# Bluetooth_UEXT.net
KiCad netlist of a schematic drawn in EAGLE
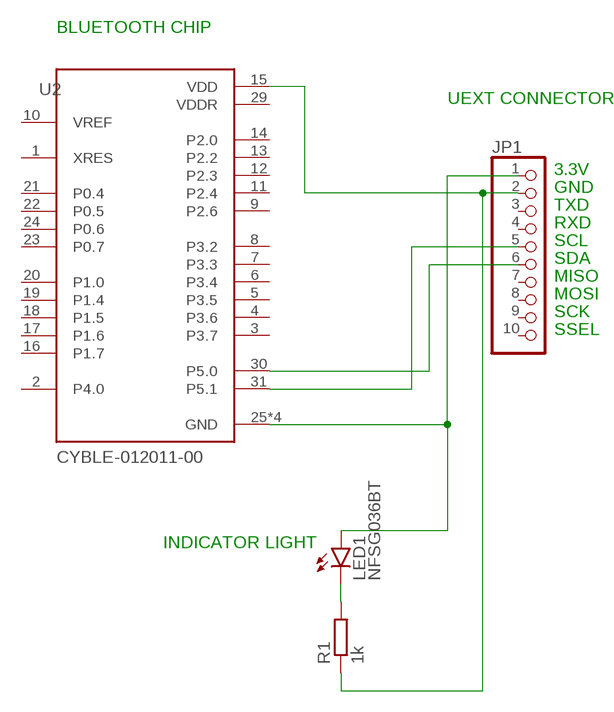
[diagram p0: schematic, sheet 1]

(export (version "E")
  (design (tool "Eeschema 10.0.6"))
  (components
    (comp (ref "JP1")
      (value "PINHD-1X10/90")
      (footprint "eagle-import:1X10_90")
      (libsource (lib "eagle-import") (part "PINHD-1X10/90"))
    )
    (comp (ref "LED1")
      (value "NFSG036BT")
      (footprint "eagle-import:NFSG036BT")
      (libsource (lib "eagle-import") (part "NFSG036BT"))
    )
    (comp (ref "R1")
      (value "1k")
      (footprint "eagle-import:M1206")
      (libsource (lib "eagle-import") (part "R-EU_M1206"))
    )
    (comp (ref "U2")
      (value "CYBLE-012011-00")
      (footprint "eagle-import:XCVR_CYBLE-012011-00")
      (fields (field (name "MF") "Cypress Semiconductor"))
      (libsource (lib "eagle-import") (part "CYBLE-012011-00"))
    )
  )
  (nets
    (net (code "1") (name "/VDDR") (class "Default")
      (node (ref "U2") (pin "29") (pinfunction "VDDR_29") (pintype "power_in"))
    )
    (net (code "2") (name "Net-(JP1-Pad1)") (class "Default")
      (node (ref "JP1") (pin "1") (pinfunction "1_1") (pintype "passive"))
      (node (ref "LED1") (pin "A") (pinfunction "A_A") (pintype "passive"))
      (node (ref "U2") (pin "25") (pinfunction "GND_25") (pintype "power_in"))
      (node (ref "U2") (pin "26") (pinfunction "GND_26") (pintype "power_in"))
      (node (ref "U2") (pin "27") (pinfunction "GND_27") (pintype "power_in"))
      (node (ref "U2") (pin "28") (pinfunction "GND_28") (pintype "power_in"))
    )
    (net (code "3") (name "Net-(LED1-PadC)") (class "Default")
      (node (ref "LED1") (pin "C") (pinfunction "C_C") (pintype "passive"))
      (node (ref "R1") (pin "2") (pinfunction "2_2") (pintype "passive"))
    )
    (net (code "4") (name "Net-(U2-P5.0)") (class "Default")
      (node (ref "JP1") (pin "6") (pinfunction "6_6") (pintype "passive"))
      (node (ref "U2") (pin "30") (pinfunction "P5.0_30") (pintype "bidirectional"))
    )
    (net (code "5") (name "Net-(U2-P5.1)") (class "Default")
      (node (ref "JP1") (pin "5") (pinfunction "5_5") (pintype "passive"))
      (node (ref "U2") (pin "31") (pinfunction "P5.1_31") (pintype "bidirectional"))
    )
    (net (code "6") (name "Net-(U2-VDD)") (class "Default")
      (node (ref "JP1") (pin "2") (pinfunction "2_2") (pintype "passive"))
      (node (ref "R1") (pin "1") (pinfunction "1_1") (pintype "passive"))
      (node (ref "U2") (pin "15") (pinfunction "VDD_15") (pintype "power_in"))
    )
    (net (code "7") (name "unconnected-(JP1-Pad3)") (class "Default")
      (node (ref "JP1") (pin "3") (pinfunction "3_3") (pintype "passive"))
    )
    (net (code "8") (name "unconnected-(JP1-Pad4)") (class "Default")
      (node (ref "JP1") (pin "4") (pinfunction "4_4") (pintype "passive"))
    )
    (net (code "9") (name "unconnected-(JP1-Pad7)") (class "Default")
      (node (ref "JP1") (pin "7") (pinfunction "7_7") (pintype "passive"))
    )
    (net (code "10") (name "unconnected-(JP1-Pad8)") (class "Default")
      (node (ref "JP1") (pin "8") (pinfunction "8_8") (pintype "passive"))
    )
    (net (code "11") (name "unconnected-(JP1-Pad9)") (class "Default")
      (node (ref "JP1") (pin "9") (pinfunction "9_9") (pintype "passive"))
    )
    (net (code "12") (name "unconnected-(JP1-Pad10)") (class "Default")
      (node (ref "JP1") (pin "10") (pinfunction "10_10") (pintype "passive"))
    )
    (net (code "13") (name "unconnected-(U2-P0.4-Pad21)") (class "Default")
      (node (ref "U2") (pin "21") (pinfunction "P0.4_21") (pintype "bidirectional"))
    )
    (net (code "14") (name "unconnected-(U2-P0.5-Pad22)") (class "Default")
      (node (ref "U2") (pin "22") (pinfunction "P0.5_22") (pintype "bidirectional"))
    )
    (net (code "15") (name "unconnected-(U2-P0.6-Pad24)") (class "Default")
      (node (ref "U2") (pin "24") (pinfunction "P0.6_24") (pintype "bidirectional"))
    )
    (net (code "16") (name "unconnected-(U2-P0.7-Pad23)") (class "Default")
      (node (ref "U2") (pin "23") (pinfunction "P0.7_23") (pintype "bidirectional"))
    )
    (net (code "17") (name "unconnected-(U2-P1.0-Pad20)") (class "Default")
      (node (ref "U2") (pin "20") (pinfunction "P1.0_20") (pintype "bidirectional"))
    )
    (net (code "18") (name "unconnected-(U2-P1.4-Pad19)") (class "Default")
      (node (ref "U2") (pin "19") (pinfunction "P1.4_19") (pintype "bidirectional"))
    )
    (net (code "19") (name "unconnected-(U2-P1.5-Pad18)") (class "Default")
      (node (ref "U2") (pin "18") (pinfunction "P1.5_18") (pintype "bidirectional"))
    )
    (net (code "20") (name "unconnected-(U2-P1.6-Pad17)") (class "Default")
      (node (ref "U2") (pin "17") (pinfunction "P1.6_17") (pintype "bidirectional"))
    )
    (net (code "21") (name "unconnected-(U2-P1.7-Pad16)") (class "Default")
      (node (ref "U2") (pin "16") (pinfunction "P1.7_16") (pintype "bidirectional"))
    )
    (net (code "22") (name "unconnected-(U2-P2.0-Pad14)") (class "Default")
      (node (ref "U2") (pin "14") (pinfunction "P2.0_14") (pintype "bidirectional"))
    )
    (net (code "23") (name "unconnected-(U2-P2.2-Pad13)") (class "Default")
      (node (ref "U2") (pin "13") (pinfunction "P2.2_13") (pintype "bidirectional"))
    )
    (net (code "24") (name "unconnected-(U2-P2.3-Pad12)") (class "Default")
      (node (ref "U2") (pin "12") (pinfunction "P2.3_12") (pintype "bidirectional"))
    )
    (net (code "25") (name "unconnected-(U2-P2.4-Pad11)") (class "Default")
      (node (ref "U2") (pin "11") (pinfunction "P2.4_11") (pintype "bidirectional"))
    )
    (net (code "26") (name "unconnected-(U2-P2.6-Pad9)") (class "Default")
      (node (ref "U2") (pin "9") (pinfunction "P2.6_9") (pintype "bidirectional"))
    )
    (net (code "27") (name "unconnected-(U2-P3.2-Pad8)") (class "Default")
      (node (ref "U2") (pin "8") (pinfunction "P3.2_8") (pintype "bidirectional"))
    )
    (net (code "28") (name "unconnected-(U2-P3.3-Pad7)") (class "Default")
      (node (ref "U2") (pin "7") (pinfunction "P3.3_7") (pintype "bidirectional"))
    )
    (net (code "29") (name "unconnected-(U2-P3.4-Pad6)") (class "Default")
      (node (ref "U2") (pin "6") (pinfunction "P3.4_6") (pintype "bidirectional"))
    )
    (net (code "30") (name "unconnected-(U2-P3.5-Pad5)") (class "Default")
      (node (ref "U2") (pin "5") (pinfunction "P3.5_5") (pintype "bidirectional"))
    )
    (net (code "31") (name "unconnected-(U2-P3.6-Pad4)") (class "Default")
      (node (ref "U2") (pin "4") (pinfunction "P3.6_4") (pintype "bidirectional"))
    )
    (net (code "32") (name "unconnected-(U2-P3.7-Pad3)") (class "Default")
      (node (ref "U2") (pin "3") (pinfunction "P3.7_3") (pintype "bidirectional"))
    )
    (net (code "33") (name "unconnected-(U2-P4.0-Pad2)") (class "Default")
      (node (ref "U2") (pin "2") (pinfunction "P4.0_2") (pintype "bidirectional"))
    )
    (net (code "34") (name "unconnected-(U2-VREF-Pad10)") (class "Default")
      (node (ref "U2") (pin "10") (pinfunction "VREF_10") (pintype "input"))
    )
    (net (code "35") (name "unconnected-(U2-XRES-Pad1)") (class "Default")
      (node (ref "U2") (pin "1") (pinfunction "XRES_1") (pintype "input"))
    )
  )
)
